# pullupcount.net
KiCad netlist of a schematic drawn in Altium Designer
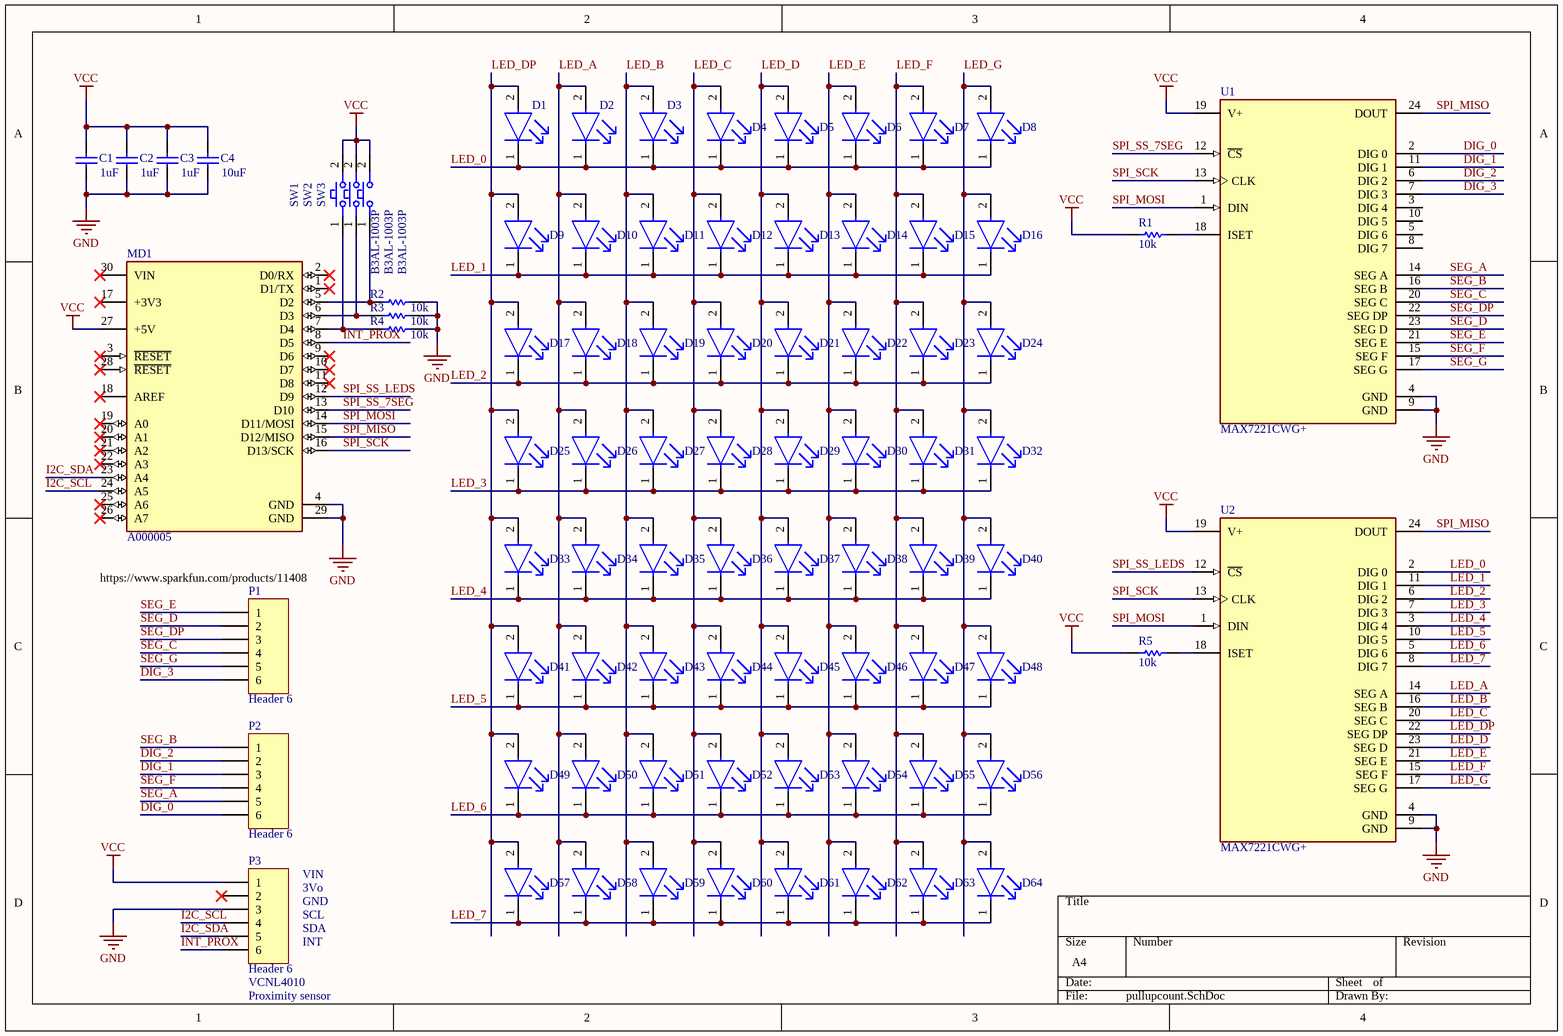
[diagram p0: pullupcount.SchDoc]

(export (version "E")
  (design (tool "Eeschema 10.0.6"))
  (components
    (comp (ref "C1")
      (value "1uF")
      (footprint "CAPC1608X90X35LL10T15")
      (fields (field (name "MANUFACTURER") "Murata") (field (name "PART NUMBER") "GRM188R61E105KA12D"))
      (libsource (lib "Altium Content Vault") (part "CAP"))
    )
    (comp (ref "C2")
      (value "1uF")
      (footprint "CAPC1608X90X35LL10T15")
      (fields (field (name "MANUFACTURER") "Murata") (field (name "PART NUMBER") "GRM188R61E105KA12D"))
      (libsource (lib "Altium Content Vault") (part "CAP"))
    )
    (comp (ref "C3")
      (value "1uF")
      (footprint "CAPC1608X90X35LL10T15")
      (fields (field (name "MANUFACTURER") "Murata") (field (name "PART NUMBER") "GRM188R61E105KA12D"))
      (libsource (lib "Altium Content Vault") (part "CAP"))
    )
    (comp (ref "C4")
      (value "10uF")
      (footprint "CAPC1608X90X35LL10T15")
      (fields (field (name "MANUFACTURER") "Murata") (field (name "PART NUMBER") "GRM188R61E105KA12D"))
      (libsource (lib "Altium Content Vault") (part "CAP"))
    )
    (comp (ref "D1")
      (value "LTST-C191TBKT")
      (footprint "FP-LTST-C191TBKT-MFG")
      (description "LED BLUE CLEAR CHIP SMD")
      (libsource (lib "Altium Content Vault") (part "8706943c75ba83719d021d2fdc84c58"))
    )
    (comp (ref "D2")
      (value "LTST-C191TBKT")
      (footprint "FP-LTST-C191TBKT-MFG")
      (description "LED BLUE CLEAR CHIP SMD")
      (libsource (lib "Altium Content Vault") (part "8706943c75ba83719d021d2fdc84c58"))
    )
    (comp (ref "D3")
      (value "LTST-C191TBKT")
      (footprint "FP-LTST-C191TBKT-MFG")
      (description "LED BLUE CLEAR CHIP SMD")
      (libsource (lib "Altium Content Vault") (part "8706943c75ba83719d021d2fdc84c58"))
    )
    (comp (ref "D4")
      (value "LTST-C191TBKT")
      (footprint "FP-LTST-C191TBKT-MFG")
      (description "LED BLUE CLEAR CHIP SMD")
      (libsource (lib "Altium Content Vault") (part "8706943c75ba83719d021d2fdc84c58"))
    )
    (comp (ref "D5")
      (value "LTST-C191TBKT")
      (footprint "FP-LTST-C191TBKT-MFG")
      (description "LED BLUE CLEAR CHIP SMD")
      (libsource (lib "Altium Content Vault") (part "8706943c75ba83719d021d2fdc84c58"))
    )
    (comp (ref "D6")
      (value "LTST-C191TBKT")
      (footprint "FP-LTST-C191TBKT-MFG")
      (description "LED BLUE CLEAR CHIP SMD")
      (libsource (lib "Altium Content Vault") (part "8706943c75ba83719d021d2fdc84c58"))
    )
    (comp (ref "D7")
      (value "LTST-C191TBKT")
      (footprint "FP-LTST-C191TBKT-MFG")
      (description "LED BLUE CLEAR CHIP SMD")
      (libsource (lib "Altium Content Vault") (part "8706943c75ba83719d021d2fdc84c58"))
    )
    (comp (ref "D8")
      (value "LTST-C191TBKT")
      (footprint "FP-LTST-C191TBKT-MFG")
      (description "LED BLUE CLEAR CHIP SMD")
      (libsource (lib "Altium Content Vault") (part "8706943c75ba83719d021d2fdc84c58"))
    )
    (comp (ref "D9")
      (value "LTST-C191TBKT")
      (footprint "FP-LTST-C191TBKT-MFG")
      (description "LED BLUE CLEAR CHIP SMD")
      (libsource (lib "Altium Content Vault") (part "8706943c75ba83719d021d2fdc84c58"))
    )
    (comp (ref "D10")
      (value "LTST-C191TBKT")
      (footprint "FP-LTST-C191TBKT-MFG")
      (description "LED BLUE CLEAR CHIP SMD")
      (libsource (lib "Altium Content Vault") (part "8706943c75ba83719d021d2fdc84c58"))
    )
    (comp (ref "D11")
      (value "LTST-C191TBKT")
      (footprint "FP-LTST-C191TBKT-MFG")
      (description "LED BLUE CLEAR CHIP SMD")
      (libsource (lib "Altium Content Vault") (part "8706943c75ba83719d021d2fdc84c58"))
    )
    (comp (ref "D12")
      (value "LTST-C191TBKT")
      (footprint "FP-LTST-C191TBKT-MFG")
      (description "LED BLUE CLEAR CHIP SMD")
      (libsource (lib "Altium Content Vault") (part "8706943c75ba83719d021d2fdc84c58"))
    )
    (comp (ref "D13")
      (value "LTST-C191TBKT")
      (footprint "FP-LTST-C191TBKT-MFG")
      (description "LED BLUE CLEAR CHIP SMD")
      (libsource (lib "Altium Content Vault") (part "8706943c75ba83719d021d2fdc84c58"))
    )
    (comp (ref "D14")
      (value "LTST-C191TBKT")
      (footprint "FP-LTST-C191TBKT-MFG")
      (description "LED BLUE CLEAR CHIP SMD")
      (libsource (lib "Altium Content Vault") (part "8706943c75ba83719d021d2fdc84c58"))
    )
    (comp (ref "D15")
      (value "LTST-C191TBKT")
      (footprint "FP-LTST-C191TBKT-MFG")
      (description "LED BLUE CLEAR CHIP SMD")
      (libsource (lib "Altium Content Vault") (part "8706943c75ba83719d021d2fdc84c58"))
    )
    (comp (ref "D16")
      (value "LTST-C191TBKT")
      (footprint "FP-LTST-C191TBKT-MFG")
      (description "LED BLUE CLEAR CHIP SMD")
      (libsource (lib "Altium Content Vault") (part "8706943c75ba83719d021d2fdc84c58"))
    )
    (comp (ref "D17")
      (value "LTST-C191TBKT")
      (footprint "FP-LTST-C191TBKT-MFG")
      (description "LED BLUE CLEAR CHIP SMD")
      (libsource (lib "Altium Content Vault") (part "8706943c75ba83719d021d2fdc84c58"))
    )
    (comp (ref "D18")
      (value "LTST-C191TBKT")
      (footprint "FP-LTST-C191TBKT-MFG")
      (description "LED BLUE CLEAR CHIP SMD")
      (libsource (lib "Altium Content Vault") (part "8706943c75ba83719d021d2fdc84c58"))
    )
    (comp (ref "D19")
      (value "LTST-C191TBKT")
      (footprint "FP-LTST-C191TBKT-MFG")
      (description "LED BLUE CLEAR CHIP SMD")
      (libsource (lib "Altium Content Vault") (part "8706943c75ba83719d021d2fdc84c58"))
    )
    (comp (ref "D20")
      (value "LTST-C191TBKT")
      (footprint "FP-LTST-C191TBKT-MFG")
      (description "LED BLUE CLEAR CHIP SMD")
      (libsource (lib "Altium Content Vault") (part "8706943c75ba83719d021d2fdc84c58"))
    )
    (comp (ref "D21")
      (value "LTST-C191TBKT")
      (footprint "FP-LTST-C191TBKT-MFG")
      (description "LED BLUE CLEAR CHIP SMD")
      (libsource (lib "Altium Content Vault") (part "8706943c75ba83719d021d2fdc84c58"))
    )
    (comp (ref "D22")
      (value "LTST-C191TBKT")
      (footprint "FP-LTST-C191TBKT-MFG")
      (description "LED BLUE CLEAR CHIP SMD")
      (libsource (lib "Altium Content Vault") (part "8706943c75ba83719d021d2fdc84c58"))
    )
    (comp (ref "D23")
      (value "LTST-C191TBKT")
      (footprint "FP-LTST-C191TBKT-MFG")
      (description "LED BLUE CLEAR CHIP SMD")
      (libsource (lib "Altium Content Vault") (part "8706943c75ba83719d021d2fdc84c58"))
    )
    (comp (ref "D24")
      (value "LTST-C191TBKT")
      (footprint "FP-LTST-C191TBKT-MFG")
      (description "LED BLUE CLEAR CHIP SMD")
      (libsource (lib "Altium Content Vault") (part "8706943c75ba83719d021d2fdc84c58"))
    )
    (comp (ref "D25")
      (value "LTST-C191TBKT")
      (footprint "FP-LTST-C191TBKT-MFG")
      (description "LED BLUE CLEAR CHIP SMD")
      (libsource (lib "Altium Content Vault") (part "8706943c75ba83719d021d2fdc84c58"))
    )
    (comp (ref "D26")
      (value "LTST-C191TBKT")
      (footprint "FP-LTST-C191TBKT-MFG")
      (description "LED BLUE CLEAR CHIP SMD")
      (libsource (lib "Altium Content Vault") (part "8706943c75ba83719d021d2fdc84c58"))
    )
    (comp (ref "D27")
      (value "LTST-C191TBKT")
      (footprint "FP-LTST-C191TBKT-MFG")
      (description "LED BLUE CLEAR CHIP SMD")
      (libsource (lib "Altium Content Vault") (part "8706943c75ba83719d021d2fdc84c58"))
    )
    (comp (ref "D28")
      (value "LTST-C191TBKT")
      (footprint "FP-LTST-C191TBKT-MFG")
      (description "LED BLUE CLEAR CHIP SMD")
      (libsource (lib "Altium Content Vault") (part "8706943c75ba83719d021d2fdc84c58"))
    )
    (comp (ref "D29")
      (value "LTST-C191TBKT")
      (footprint "FP-LTST-C191TBKT-MFG")
      (description "LED BLUE CLEAR CHIP SMD")
      (libsource (lib "Altium Content Vault") (part "8706943c75ba83719d021d2fdc84c58"))
    )
    (comp (ref "D30")
      (value "LTST-C191TBKT")
      (footprint "FP-LTST-C191TBKT-MFG")
      (description "LED BLUE CLEAR CHIP SMD")
      (libsource (lib "Altium Content Vault") (part "8706943c75ba83719d021d2fdc84c58"))
    )
    (comp (ref "D31")
      (value "LTST-C191TBKT")
      (footprint "FP-LTST-C191TBKT-MFG")
      (description "LED BLUE CLEAR CHIP SMD")
      (libsource (lib "Altium Content Vault") (part "8706943c75ba83719d021d2fdc84c58"))
    )
    (comp (ref "D32")
      (value "LTST-C191TBKT")
      (footprint "FP-LTST-C191TBKT-MFG")
      (description "LED BLUE CLEAR CHIP SMD")
      (libsource (lib "Altium Content Vault") (part "8706943c75ba83719d021d2fdc84c58"))
    )
    (comp (ref "D33")
      (value "LTST-C191TBKT")
      (footprint "FP-LTST-C191TBKT-MFG")
      (description "LED BLUE CLEAR CHIP SMD")
      (libsource (lib "Altium Content Vault") (part "8706943c75ba83719d021d2fdc84c58"))
    )
    (comp (ref "D34")
      (value "LTST-C191TBKT")
      (footprint "FP-LTST-C191TBKT-MFG")
      (description "LED BLUE CLEAR CHIP SMD")
      (libsource (lib "Altium Content Vault") (part "8706943c75ba83719d021d2fdc84c58"))
    )
    (comp (ref "D35")
      (value "LTST-C191TBKT")
      (footprint "FP-LTST-C191TBKT-MFG")
      (description "LED BLUE CLEAR CHIP SMD")
      (libsource (lib "Altium Content Vault") (part "8706943c75ba83719d021d2fdc84c58"))
    )
    (comp (ref "D36")
      (value "LTST-C191TBKT")
      (footprint "FP-LTST-C191TBKT-MFG")
      (description "LED BLUE CLEAR CHIP SMD")
      (libsource (lib "Altium Content Vault") (part "8706943c75ba83719d021d2fdc84c58"))
    )
    (comp (ref "D37")
      (value "LTST-C191TBKT")
      (footprint "FP-LTST-C191TBKT-MFG")
      (description "LED BLUE CLEAR CHIP SMD")
      (libsource (lib "Altium Content Vault") (part "8706943c75ba83719d021d2fdc84c58"))
    )
    (comp (ref "D38")
      (value "LTST-C191TBKT")
      (footprint "FP-LTST-C191TBKT-MFG")
      (description "LED BLUE CLEAR CHIP SMD")
      (libsource (lib "Altium Content Vault") (part "8706943c75ba83719d021d2fdc84c58"))
    )
    (comp (ref "D39")
      (value "LTST-C191TBKT")
      (footprint "FP-LTST-C191TBKT-MFG")
      (description "LED BLUE CLEAR CHIP SMD")
      (libsource (lib "Altium Content Vault") (part "8706943c75ba83719d021d2fdc84c58"))
    )
    (comp (ref "D40")
      (value "LTST-C191TBKT")
      (footprint "FP-LTST-C191TBKT-MFG")
      (description "LED BLUE CLEAR CHIP SMD")
      (libsource (lib "Altium Content Vault") (part "8706943c75ba83719d021d2fdc84c58"))
    )
    (comp (ref "D41")
      (value "LTST-C191TBKT")
      (footprint "FP-LTST-C191TBKT-MFG")
      (description "LED BLUE CLEAR CHIP SMD")
      (libsource (lib "Altium Content Vault") (part "8706943c75ba83719d021d2fdc84c58"))
    )
    (comp (ref "D42")
      (value "LTST-C191TBKT")
      (footprint "FP-LTST-C191TBKT-MFG")
      (description "LED BLUE CLEAR CHIP SMD")
      (libsource (lib "Altium Content Vault") (part "8706943c75ba83719d021d2fdc84c58"))
    )
    (comp (ref "D43")
      (value "LTST-C191TBKT")
      (footprint "FP-LTST-C191TBKT-MFG")
      (description "LED BLUE CLEAR CHIP SMD")
      (libsource (lib "Altium Content Vault") (part "8706943c75ba83719d021d2fdc84c58"))
    )
    (comp (ref "D44")
      (value "LTST-C191TBKT")
      (footprint "FP-LTST-C191TBKT-MFG")
      (description "LED BLUE CLEAR CHIP SMD")
      (libsource (lib "Altium Content Vault") (part "8706943c75ba83719d021d2fdc84c58"))
    )
    (comp (ref "D45")
      (value "LTST-C191TBKT")
      (footprint "FP-LTST-C191TBKT-MFG")
      (description "LED BLUE CLEAR CHIP SMD")
      (libsource (lib "Altium Content Vault") (part "8706943c75ba83719d021d2fdc84c58"))
    )
    (comp (ref "D46")
      (value "LTST-C191TBKT")
      (footprint "FP-LTST-C191TBKT-MFG")
      (description "LED BLUE CLEAR CHIP SMD")
      (libsource (lib "Altium Content Vault") (part "8706943c75ba83719d021d2fdc84c58"))
    )
    (comp (ref "D47")
      (value "LTST-C191TBKT")
      (footprint "FP-LTST-C191TBKT-MFG")
      (description "LED BLUE CLEAR CHIP SMD")
      (libsource (lib "Altium Content Vault") (part "8706943c75ba83719d021d2fdc84c58"))
    )
    (comp (ref "D48")
      (value "LTST-C191TBKT")
      (footprint "FP-LTST-C191TBKT-MFG")
      (description "LED BLUE CLEAR CHIP SMD")
      (libsource (lib "Altium Content Vault") (part "8706943c75ba83719d021d2fdc84c58"))
    )
    (comp (ref "D49")
      (value "LTST-C191TBKT")
      (footprint "FP-LTST-C191TBKT-MFG")
      (description "LED BLUE CLEAR CHIP SMD")
      (libsource (lib "Altium Content Vault") (part "8706943c75ba83719d021d2fdc84c58"))
    )
    (comp (ref "D50")
      (value "LTST-C191TBKT")
      (footprint "FP-LTST-C191TBKT-MFG")
      (description "LED BLUE CLEAR CHIP SMD")
      (libsource (lib "Altium Content Vault") (part "8706943c75ba83719d021d2fdc84c58"))
    )
    (comp (ref "D51")
      (value "LTST-C191TBKT")
      (footprint "FP-LTST-C191TBKT-MFG")
      (description "LED BLUE CLEAR CHIP SMD")
      (libsource (lib "Altium Content Vault") (part "8706943c75ba83719d021d2fdc84c58"))
    )
    (comp (ref "D52")
      (value "LTST-C191TBKT")
      (footprint "FP-LTST-C191TBKT-MFG")
      (description "LED BLUE CLEAR CHIP SMD")
      (libsource (lib "Altium Content Vault") (part "8706943c75ba83719d021d2fdc84c58"))
    )
    (comp (ref "D53")
      (value "LTST-C191TBKT")
      (footprint "FP-LTST-C191TBKT-MFG")
      (description "LED BLUE CLEAR CHIP SMD")
      (libsource (lib "Altium Content Vault") (part "8706943c75ba83719d021d2fdc84c58"))
    )
    (comp (ref "D54")
      (value "LTST-C191TBKT")
      (footprint "FP-LTST-C191TBKT-MFG")
      (description "LED BLUE CLEAR CHIP SMD")
      (libsource (lib "Altium Content Vault") (part "8706943c75ba83719d021d2fdc84c58"))
    )
    (comp (ref "D55")
      (value "LTST-C191TBKT")
      (footprint "FP-LTST-C191TBKT-MFG")
      (description "LED BLUE CLEAR CHIP SMD")
      (libsource (lib "Altium Content Vault") (part "8706943c75ba83719d021d2fdc84c58"))
    )
    (comp (ref "D56")
      (value "LTST-C191TBKT")
      (footprint "FP-LTST-C191TBKT-MFG")
      (description "LED BLUE CLEAR CHIP SMD")
      (libsource (lib "Altium Content Vault") (part "8706943c75ba83719d021d2fdc84c58"))
    )
    (comp (ref "D57")
      (value "LTST-C191TBKT")
      (footprint "FP-LTST-C191TBKT-MFG")
      (description "LED BLUE CLEAR CHIP SMD")
      (libsource (lib "Altium Content Vault") (part "8706943c75ba83719d021d2fdc84c58"))
    )
    (comp (ref "D58")
      (value "LTST-C191TBKT")
      (footprint "FP-LTST-C191TBKT-MFG")
      (description "LED BLUE CLEAR CHIP SMD")
      (libsource (lib "Altium Content Vault") (part "8706943c75ba83719d021d2fdc84c58"))
    )
    (comp (ref "D59")
      (value "LTST-C191TBKT")
      (footprint "FP-LTST-C191TBKT-MFG")
      (description "LED BLUE CLEAR CHIP SMD")
      (libsource (lib "Altium Content Vault") (part "8706943c75ba83719d021d2fdc84c58"))
    )
    (comp (ref "D60")
      (value "LTST-C191TBKT")
      (footprint "FP-LTST-C191TBKT-MFG")
      (description "LED BLUE CLEAR CHIP SMD")
      (libsource (lib "Altium Content Vault") (part "8706943c75ba83719d021d2fdc84c58"))
    )
    (comp (ref "D61")
      (value "LTST-C191TBKT")
      (footprint "FP-LTST-C191TBKT-MFG")
      (description "LED BLUE CLEAR CHIP SMD")
      (libsource (lib "Altium Content Vault") (part "8706943c75ba83719d021d2fdc84c58"))
    )
    (comp (ref "D62")
      (value "LTST-C191TBKT")
      (footprint "FP-LTST-C191TBKT-MFG")
      (description "LED BLUE CLEAR CHIP SMD")
      (libsource (lib "Altium Content Vault") (part "8706943c75ba83719d021d2fdc84c58"))
    )
    (comp (ref "D63")
      (value "LTST-C191TBKT")
      (footprint "FP-LTST-C191TBKT-MFG")
      (description "LED BLUE CLEAR CHIP SMD")
      (libsource (lib "Altium Content Vault") (part "8706943c75ba83719d021d2fdc84c58"))
    )
    (comp (ref "D64")
      (value "LTST-C191TBKT")
      (footprint "FP-LTST-C191TBKT-MFG")
      (description "LED BLUE CLEAR CHIP SMD")
      (libsource (lib "Altium Content Vault") (part "8706943c75ba83719d021d2fdc84c58"))
    )
    (comp (ref "MD1")
      (value "A000005")
      (footprint "FP-A000005-MFG")
      (description "ARDUINO NANO ATMEGA328 EVAL BRD")
      (libsource (lib "Altium Content Vault") (part "d190c066e99afd1c6882cf92e11b2cc"))
    )
    (comp (ref "P1")
      (value "Header 6")
      (footprint "HDR1X6")
      (description "Header, 6-Pin")
      (fields (field (name "PUBLISHER") "Altium Limited"))
      (libsource (lib "Miscellaneous Connectors") (part "Header 6"))
    )
    (comp (ref "P2")
      (value "Header 6")
      (footprint "HDR1X6")
      (description "Header, 6-Pin")
      (fields (field (name "PUBLISHER") "Altium Limited"))
      (libsource (lib "Miscellaneous Connectors") (part "Header 6"))
    )
    (comp (ref "P3")
      (value "Header 6")
      (footprint "HDR1X6")
      (description "Header, 6-Pin")
      (fields (field (name "PUBLISHER") "Altium Limited"))
      (libsource (lib "Miscellaneous Connectors") (part "Header 6"))
    )
    (comp (ref "R1")
      (value "10k")
      (footprint "RESC1609X50X30NL8T20")
      (description "Chip Resistor, 10 KOhm, +/- 1%, 100 mW, -55 to 155 degC, 0603 (1608 Metric), RoHS, Tape and Reel")
      (fields (field (name "MANUFACTURER") "Vishay Semiconductor"))
      (libsource (lib "Altium Content Vault") (part "RES-2"))
    )
    (comp (ref "R2")
      (value "10k")
      (footprint "RESC1609X50X30NL8T20")
      (description "Chip Resistor, 10 KOhm, +/- 1%, 100 mW, -55 to 155 degC, 0603 (1608 Metric), RoHS, Tape and Reel")
      (fields (field (name "MANUFACTURER") "Vishay Semiconductor"))
      (libsource (lib "Altium Content Vault") (part "RES-2"))
    )
    (comp (ref "R3")
      (value "10k")
      (footprint "RESC1609X50X30NL8T20")
      (description "Chip Resistor, 10 KOhm, +/- 1%, 100 mW, -55 to 155 degC, 0603 (1608 Metric), RoHS, Tape and Reel")
      (fields (field (name "MANUFACTURER") "Vishay Semiconductor"))
      (libsource (lib "Altium Content Vault") (part "RES-2"))
    )
    (comp (ref "R4")
      (value "10k")
      (footprint "RESC1609X50X30NL8T20")
      (description "Chip Resistor, 10 KOhm, +/- 1%, 100 mW, -55 to 155 degC, 0603 (1608 Metric), RoHS, Tape and Reel")
      (fields (field (name "MANUFACTURER") "Vishay Semiconductor"))
      (libsource (lib "Altium Content Vault") (part "RES-2"))
    )
    (comp (ref "R5")
      (value "10k")
      (footprint "RESC1609X50X30NL8T20")
      (description "Chip Resistor, 10 KOhm, +/- 1%, 100 mW, -55 to 155 degC, 0603 (1608 Metric), RoHS, Tape and Reel")
      (fields (field (name "MANUFACTURER") "Vishay Semiconductor"))
      (libsource (lib "Altium Content Vault") (part "RES-2"))
    )
    (comp (ref "SW1")
      (value "B3AL-1003P")
      (footprint "FP-B3AL-1003P-MFG")
      (description "SWITCH TACTILE SPST-NO 0.05A 16V")
      (libsource (lib "Altium Content Vault") (part "69e8347f6a24c021ef43a914a4df441"))
    )
    (comp (ref "SW2")
      (value "B3AL-1003P")
      (footprint "FP-B3AL-1003P-MFG")
      (description "SWITCH TACTILE SPST-NO 0.05A 16V")
      (libsource (lib "Altium Content Vault") (part "69e8347f6a24c021ef43a914a4df441"))
    )
    (comp (ref "SW3")
      (value "B3AL-1003P")
      (footprint "FP-B3AL-1003P-MFG")
      (description "SWITCH TACTILE SPST-NO 0.05A 16V")
      (libsource (lib "Altium Content Vault") (part "69e8347f6a24c021ef43a914a4df441"))
    )
    (comp (ref "U1")
      (value "MAX7221CWG+")
      (footprint "FP-W24-1-MFG")
      (description "IC DRVR 7 SEGMNT 8 DIGIT 24SOIC")
      (fields
        (field (name "MANUFACTURER") "Maxim Integrated")
        (field (name "OCTOPART") "https://octopart.com/max7221cwg%2B-maxim+integrated-39581478")
      )
      (libsource (lib "Altium Content Vault") (part "a71a82daf51cffeecc638e415d68d56"))
    )
    (comp (ref "U2")
      (value "MAX7221CWG+")
      (footprint "FP-W24-1-MFG")
      (description "IC DRVR 7 SEGMNT 8 DIGIT 24SOIC")
      (fields
        (field (name "MANUFACTURER") "Maxim Integrated")
        (field (name "OCTOPART") "https://octopart.com/max7221cwg%2B-maxim+integrated-39581478")
      )
      (libsource (lib "Altium Content Vault") (part "a71a82daf51cffeecc638e415d68d56"))
    )
  )
  (nets
    (net (code "1") (name "/DIG_0") (class "Default")
      (node (ref "P2") (pin "6") (pinfunction "6_6") (pintype "passive"))
      (node (ref "U1") (pin "2") (pinfunction "DIG_0_2") (pintype "passive"))
    )
    (net (code "2") (name "/DIG_1") (class "Default")
      (node (ref "P2") (pin "3") (pinfunction "3_3") (pintype "passive"))
      (node (ref "U1") (pin "11") (pinfunction "DIG_1_11") (pintype "passive"))
    )
    (net (code "3") (name "/DIG_2") (class "Default")
      (node (ref "P2") (pin "2") (pinfunction "2_2") (pintype "passive"))
      (node (ref "U1") (pin "6") (pinfunction "DIG_2_6") (pintype "passive"))
    )
    (net (code "4") (name "/DIG_3") (class "Default")
      (node (ref "P1") (pin "6") (pinfunction "6_6") (pintype "passive"))
      (node (ref "U1") (pin "7") (pinfunction "DIG_3_7") (pintype "passive"))
    )
    (net (code "5") (name "/I2C_SCL") (class "Default")
      (node (ref "MD1") (pin "24") (pinfunction "A5_24") (pintype "bidirectional"))
      (node (ref "P3") (pin "4") (pinfunction "4_4") (pintype "passive"))
    )
    (net (code "6") (name "/I2C_SDA") (class "Default")
      (node (ref "MD1") (pin "23") (pinfunction "A4_23") (pintype "bidirectional"))
      (node (ref "P3") (pin "5") (pinfunction "5_5") (pintype "passive"))
    )
    (net (code "7") (name "/INT_PROX") (class "Default")
      (node (ref "MD1") (pin "8") (pinfunction "D5_8") (pintype "bidirectional"))
      (node (ref "P3") (pin "6") (pinfunction "6_6") (pintype "passive"))
    )
    (net (code "8") (name "/LED_0") (class "Default")
      (node (ref "D1") (pin "1") (pinfunction "C_1") (pintype "passive"))
      (node (ref "D2") (pin "1") (pinfunction "C_1") (pintype "passive"))
      (node (ref "D3") (pin "1") (pinfunction "C_1") (pintype "passive"))
      (node (ref "D4") (pin "1") (pinfunction "C_1") (pintype "passive"))
      (node (ref "D5") (pin "1") (pinfunction "C_1") (pintype "passive"))
      (node (ref "D6") (pin "1") (pinfunction "C_1") (pintype "passive"))
      (node (ref "D7") (pin "1") (pinfunction "C_1") (pintype "passive"))
      (node (ref "D8") (pin "1") (pinfunction "C_1") (pintype "passive"))
      (node (ref "U2") (pin "2") (pinfunction "DIG_0_2") (pintype "passive"))
    )
    (net (code "9") (name "/LED_1") (class "Default")
      (node (ref "D10") (pin "1") (pinfunction "C_1") (pintype "passive"))
      (node (ref "D11") (pin "1") (pinfunction "C_1") (pintype "passive"))
      (node (ref "D12") (pin "1") (pinfunction "C_1") (pintype "passive"))
      (node (ref "D13") (pin "1") (pinfunction "C_1") (pintype "passive"))
      (node (ref "D14") (pin "1") (pinfunction "C_1") (pintype "passive"))
      (node (ref "D15") (pin "1") (pinfunction "C_1") (pintype "passive"))
      (node (ref "D16") (pin "1") (pinfunction "C_1") (pintype "passive"))
      (node (ref "D9") (pin "1") (pinfunction "C_1") (pintype "passive"))
      (node (ref "U2") (pin "11") (pinfunction "DIG_1_11") (pintype "passive"))
    )
    (net (code "10") (name "/LED_2") (class "Default")
      (node (ref "D17") (pin "1") (pinfunction "C_1") (pintype "passive"))
      (node (ref "D18") (pin "1") (pinfunction "C_1") (pintype "passive"))
      (node (ref "D19") (pin "1") (pinfunction "C_1") (pintype "passive"))
      (node (ref "D20") (pin "1") (pinfunction "C_1") (pintype "passive"))
      (node (ref "D21") (pin "1") (pinfunction "C_1") (pintype "passive"))
      (node (ref "D22") (pin "1") (pinfunction "C_1") (pintype "passive"))
      (node (ref "D23") (pin "1") (pinfunction "C_1") (pintype "passive"))
      (node (ref "D24") (pin "1") (pinfunction "C_1") (pintype "passive"))
      (node (ref "U2") (pin "6") (pinfunction "DIG_2_6") (pintype "passive"))
    )
    (net (code "11") (name "/LED_3") (class "Default")
      (node (ref "D25") (pin "1") (pinfunction "C_1") (pintype "passive"))
      (node (ref "D26") (pin "1") (pinfunction "C_1") (pintype "passive"))
      (node (ref "D27") (pin "1") (pinfunction "C_1") (pintype "passive"))
      (node (ref "D28") (pin "1") (pinfunction "C_1") (pintype "passive"))
      (node (ref "D29") (pin "1") (pinfunction "C_1") (pintype "passive"))
      (node (ref "D30") (pin "1") (pinfunction "C_1") (pintype "passive"))
      (node (ref "D31") (pin "1") (pinfunction "C_1") (pintype "passive"))
      (node (ref "D32") (pin "1") (pinfunction "C_1") (pintype "passive"))
      (node (ref "U2") (pin "7") (pinfunction "DIG_3_7") (pintype "passive"))
    )
    (net (code "12") (name "/LED_4") (class "Default")
      (node (ref "D33") (pin "1") (pinfunction "C_1") (pintype "passive"))
      (node (ref "D34") (pin "1") (pinfunction "C_1") (pintype "passive"))
      (node (ref "D35") (pin "1") (pinfunction "C_1") (pintype "passive"))
      (node (ref "D36") (pin "1") (pinfunction "C_1") (pintype "passive"))
      (node (ref "D37") (pin "1") (pinfunction "C_1") (pintype "passive"))
      (node (ref "D38") (pin "1") (pinfunction "C_1") (pintype "passive"))
      (node (ref "D39") (pin "1") (pinfunction "C_1") (pintype "passive"))
      (node (ref "D40") (pin "1") (pinfunction "C_1") (pintype "passive"))
      (node (ref "U2") (pin "3") (pinfunction "DIG_4_3") (pintype "passive"))
    )
    (net (code "13") (name "/LED_5") (class "Default")
      (node (ref "D41") (pin "1") (pinfunction "C_1") (pintype "passive"))
      (node (ref "D42") (pin "1") (pinfunction "C_1") (pintype "passive"))
      (node (ref "D43") (pin "1") (pinfunction "C_1") (pintype "passive"))
      (node (ref "D44") (pin "1") (pinfunction "C_1") (pintype "passive"))
      (node (ref "D45") (pin "1") (pinfunction "C_1") (pintype "passive"))
      (node (ref "D46") (pin "1") (pinfunction "C_1") (pintype "passive"))
      (node (ref "D47") (pin "1") (pinfunction "C_1") (pintype "passive"))
      (node (ref "D48") (pin "1") (pinfunction "C_1") (pintype "passive"))
      (node (ref "U2") (pin "10") (pinfunction "DIG_5_10") (pintype "passive"))
    )
    (net (code "14") (name "/LED_6") (class "Default")
      (node (ref "D49") (pin "1") (pinfunction "C_1") (pintype "passive"))
      (node (ref "D50") (pin "1") (pinfunction "C_1") (pintype "passive"))
      (node (ref "D51") (pin "1") (pinfunction "C_1") (pintype "passive"))
      (node (ref "D52") (pin "1") (pinfunction "C_1") (pintype "passive"))
      (node (ref "D53") (pin "1") (pinfunction "C_1") (pintype "passive"))
      (node (ref "D54") (pin "1") (pinfunction "C_1") (pintype "passive"))
      (node (ref "D55") (pin "1") (pinfunction "C_1") (pintype "passive"))
      (node (ref "D56") (pin "1") (pinfunction "C_1") (pintype "passive"))
      (node (ref "U2") (pin "5") (pinfunction "DIG_6_5") (pintype "passive"))
    )
    (net (code "15") (name "/LED_7") (class "Default")
      (node (ref "D57") (pin "1") (pinfunction "C_1") (pintype "passive"))
      (node (ref "D58") (pin "1") (pinfunction "C_1") (pintype "passive"))
      (node (ref "D59") (pin "1") (pinfunction "C_1") (pintype "passive"))
      (node (ref "D60") (pin "1") (pinfunction "C_1") (pintype "passive"))
      (node (ref "D61") (pin "1") (pinfunction "C_1") (pintype "passive"))
      (node (ref "D62") (pin "1") (pinfunction "C_1") (pintype "passive"))
      (node (ref "D63") (pin "1") (pinfunction "C_1") (pintype "passive"))
      (node (ref "D64") (pin "1") (pinfunction "C_1") (pintype "passive"))
      (node (ref "U2") (pin "8") (pinfunction "DIG_7_8") (pintype "passive"))
    )
    (net (code "16") (name "/LED_A") (class "Default")
      (node (ref "D10") (pin "2") (pinfunction "A_2") (pintype "passive"))
      (node (ref "D18") (pin "2") (pinfunction "A_2") (pintype "passive"))
      (node (ref "D2") (pin "2") (pinfunction "A_2") (pintype "passive"))
      (node (ref "D26") (pin "2") (pinfunction "A_2") (pintype "passive"))
      (node (ref "D34") (pin "2") (pinfunction "A_2") (pintype "passive"))
      (node (ref "D42") (pin "2") (pinfunction "A_2") (pintype "passive"))
      (node (ref "D50") (pin "2") (pinfunction "A_2") (pintype "passive"))
      (node (ref "D58") (pin "2") (pinfunction "A_2") (pintype "passive"))
      (node (ref "U2") (pin "14") (pinfunction "SEG_A_14") (pintype "passive"))
    )
    (net (code "17") (name "/LED_B") (class "Default")
      (node (ref "D11") (pin "2") (pinfunction "A_2") (pintype "passive"))
      (node (ref "D19") (pin "2") (pinfunction "A_2") (pintype "passive"))
      (node (ref "D27") (pin "2") (pinfunction "A_2") (pintype "passive"))
      (node (ref "D3") (pin "2") (pinfunction "A_2") (pintype "passive"))
      (node (ref "D35") (pin "2") (pinfunction "A_2") (pintype "passive"))
      (node (ref "D43") (pin "2") (pinfunction "A_2") (pintype "passive"))
      (node (ref "D51") (pin "2") (pinfunction "A_2") (pintype "passive"))
      (node (ref "D59") (pin "2") (pinfunction "A_2") (pintype "passive"))
      (node (ref "U2") (pin "16") (pinfunction "SEG_B_16") (pintype "passive"))
    )
    (net (code "18") (name "/LED_C") (class "Default")
      (node (ref "D12") (pin "2") (pinfunction "A_2") (pintype "passive"))
      (node (ref "D20") (pin "2") (pinfunction "A_2") (pintype "passive"))
      (node (ref "D28") (pin "2") (pinfunction "A_2") (pintype "passive"))
      (node (ref "D36") (pin "2") (pinfunction "A_2") (pintype "passive"))
      (node (ref "D4") (pin "2") (pinfunction "A_2") (pintype "passive"))
      (node (ref "D44") (pin "2") (pinfunction "A_2") (pintype "passive"))
      (node (ref "D52") (pin "2") (pinfunction "A_2") (pintype "passive"))
      (node (ref "D60") (pin "2") (pinfunction "A_2") (pintype "passive"))
      (node (ref "U2") (pin "20") (pinfunction "SEG_C_20") (pintype "passive"))
    )
    (net (code "19") (name "/LED_D") (class "Default")
      (node (ref "D13") (pin "2") (pinfunction "A_2") (pintype "passive"))
      (node (ref "D21") (pin "2") (pinfunction "A_2") (pintype "passive"))
      (node (ref "D29") (pin "2") (pinfunction "A_2") (pintype "passive"))
      (node (ref "D37") (pin "2") (pinfunction "A_2") (pintype "passive"))
      (node (ref "D45") (pin "2") (pinfunction "A_2") (pintype "passive"))
      (node (ref "D5") (pin "2") (pinfunction "A_2") (pintype "passive"))
      (node (ref "D53") (pin "2") (pinfunction "A_2") (pintype "passive"))
      (node (ref "D61") (pin "2") (pinfunction "A_2") (pintype "passive"))
      (node (ref "U2") (pin "23") (pinfunction "SEG_D_23") (pintype "passive"))
    )
    (net (code "20") (name "/LED_DP") (class "Default")
      (node (ref "D1") (pin "2") (pinfunction "A_2") (pintype "passive"))
      (node (ref "D17") (pin "2") (pinfunction "A_2") (pintype "passive"))
      (node (ref "D25") (pin "2") (pinfunction "A_2") (pintype "passive"))
      (node (ref "D33") (pin "2") (pinfunction "A_2") (pintype "passive"))
      (node (ref "D41") (pin "2") (pinfunction "A_2") (pintype "passive"))
      (node (ref "D49") (pin "2") (pinfunction "A_2") (pintype "passive"))
      (node (ref "D57") (pin "2") (pinfunction "A_2") (pintype "passive"))
      (node (ref "D9") (pin "2") (pinfunction "A_2") (pintype "passive"))
      (node (ref "U2") (pin "22") (pinfunction "SEG_DP_22") (pintype "passive"))
    )
    (net (code "21") (name "/LED_E") (class "Default")
      (node (ref "D14") (pin "2") (pinfunction "A_2") (pintype "passive"))
      (node (ref "D22") (pin "2") (pinfunction "A_2") (pintype "passive"))
      (node (ref "D30") (pin "2") (pinfunction "A_2") (pintype "passive"))
      (node (ref "D38") (pin "2") (pinfunction "A_2") (pintype "passive"))
      (node (ref "D46") (pin "2") (pinfunction "A_2") (pintype "passive"))
      (node (ref "D54") (pin "2") (pinfunction "A_2") (pintype "passive"))
      (node (ref "D6") (pin "2") (pinfunction "A_2") (pintype "passive"))
      (node (ref "D62") (pin "2") (pinfunction "A_2") (pintype "passive"))
      (node (ref "U2") (pin "21") (pinfunction "SEG_E_21") (pintype "passive"))
    )
    (net (code "22") (name "/LED_F") (class "Default")
      (node (ref "D15") (pin "2") (pinfunction "A_2") (pintype "passive"))
      (node (ref "D23") (pin "2") (pinfunction "A_2") (pintype "passive"))
      (node (ref "D31") (pin "2") (pinfunction "A_2") (pintype "passive"))
      (node (ref "D39") (pin "2") (pinfunction "A_2") (pintype "passive"))
      (node (ref "D47") (pin "2") (pinfunction "A_2") (pintype "passive"))
      (node (ref "D55") (pin "2") (pinfunction "A_2") (pintype "passive"))
      (node (ref "D63") (pin "2") (pinfunction "A_2") (pintype "passive"))
      (node (ref "D7") (pin "2") (pinfunction "A_2") (pintype "passive"))
      (node (ref "U2") (pin "15") (pinfunction "SEG_F_15") (pintype "passive"))
    )
    (net (code "23") (name "/LED_G") (class "Default")
      (node (ref "D16") (pin "2") (pinfunction "A_2") (pintype "passive"))
      (node (ref "D24") (pin "2") (pinfunction "A_2") (pintype "passive"))
      (node (ref "D32") (pin "2") (pinfunction "A_2") (pintype "passive"))
      (node (ref "D40") (pin "2") (pinfunction "A_2") (pintype "passive"))
      (node (ref "D48") (pin "2") (pinfunction "A_2") (pintype "passive"))
      (node (ref "D56") (pin "2") (pinfunction "A_2") (pintype "passive"))
      (node (ref "D64") (pin "2") (pinfunction "A_2") (pintype "passive"))
      (node (ref "D8") (pin "2") (pinfunction "A_2") (pintype "passive"))
      (node (ref "U2") (pin "17") (pinfunction "SEG_G_17") (pintype "passive"))
    )
    (net (code "24") (name "/SEG_A") (class "Default")
      (node (ref "P2") (pin "5") (pinfunction "5_5") (pintype "passive"))
      (node (ref "U1") (pin "14") (pinfunction "SEG_A_14") (pintype "passive"))
    )
    (net (code "25") (name "/SEG_B") (class "Default")
      (node (ref "P2") (pin "1") (pinfunction "1_1") (pintype "passive"))
      (node (ref "U1") (pin "16") (pinfunction "SEG_B_16") (pintype "passive"))
    )
    (net (code "26") (name "/SEG_C") (class "Default")
      (node (ref "P1") (pin "4") (pinfunction "4_4") (pintype "passive"))
      (node (ref "U1") (pin "20") (pinfunction "SEG_C_20") (pintype "passive"))
    )
    (net (code "27") (name "/SEG_D") (class "Default")
      (node (ref "P1") (pin "2") (pinfunction "2_2") (pintype "passive"))
      (node (ref "U1") (pin "23") (pinfunction "SEG_D_23") (pintype "passive"))
    )
    (net (code "28") (name "/SEG_DP") (class "Default")
      (node (ref "P1") (pin "3") (pinfunction "3_3") (pintype "passive"))
      (node (ref "U1") (pin "22") (pinfunction "SEG_DP_22") (pintype "passive"))
    )
    (net (code "29") (name "/SEG_E") (class "Default")
      (node (ref "P1") (pin "1") (pinfunction "1_1") (pintype "passive"))
      (node (ref "U1") (pin "21") (pinfunction "SEG_E_21") (pintype "passive"))
    )
    (net (code "30") (name "/SEG_F") (class "Default")
      (node (ref "P2") (pin "4") (pinfunction "4_4") (pintype "passive"))
      (node (ref "U1") (pin "15") (pinfunction "SEG_F_15") (pintype "passive"))
    )
    (net (code "31") (name "/SEG_G") (class "Default")
      (node (ref "P1") (pin "5") (pinfunction "5_5") (pintype "passive"))
      (node (ref "U1") (pin "17") (pinfunction "SEG_G_17") (pintype "passive"))
    )
    (net (code "32") (name "/SPI_MISO") (class "Default")
      (node (ref "MD1") (pin "15") (pinfunction "D12/MISO_15") (pintype "bidirectional"))
      (node (ref "U1") (pin "24") (pinfunction "DOUT_24") (pintype "passive"))
      (node (ref "U2") (pin "24") (pinfunction "DOUT_24") (pintype "passive"))
    )
    (net (code "33") (name "/SPI_MOSI") (class "Default")
      (node (ref "MD1") (pin "14") (pinfunction "D11/MOSI_14") (pintype "bidirectional"))
      (node (ref "U1") (pin "1") (pinfunction "DIN_1") (pintype "input"))
      (node (ref "U2") (pin "1") (pinfunction "DIN_1") (pintype "input"))
    )
    (net (code "34") (name "/SPI_SCK") (class "Default")
      (node (ref "MD1") (pin "16") (pinfunction "D13/SCK_16") (pintype "bidirectional"))
      (node (ref "U1") (pin "13") (pinfunction "CLK_13") (pintype "input"))
      (node (ref "U2") (pin "13") (pinfunction "CLK_13") (pintype "input"))
    )
    (net (code "35") (name "/SPI_SS_7SEG") (class "Default")
      (node (ref "MD1") (pin "13") (pinfunction "D10_13") (pintype "bidirectional"))
      (node (ref "U1") (pin "12") (pinfunction "~{CS}_12") (pintype "input"))
    )
    (net (code "36") (name "/SPI_SS_LEDS") (class "Default")
      (node (ref "MD1") (pin "12") (pinfunction "D9_12") (pintype "bidirectional"))
      (node (ref "U2") (pin "12") (pinfunction "~{CS}_12") (pintype "input"))
    )
    (net (code "37") (name "GND") (class "Default")
      (node (ref "C1") (pin "1") (pinfunction "1_1") (pintype "passive"))
      (node (ref "C2") (pin "1") (pinfunction "1_1") (pintype "passive"))
      (node (ref "C3") (pin "1") (pinfunction "1_1") (pintype "passive"))
      (node (ref "C4") (pin "1") (pinfunction "1_1") (pintype "passive"))
      (node (ref "MD1") (pin "29") (pinfunction "GND_29") (pintype "power_in"))
      (node (ref "MD1") (pin "4") (pinfunction "GND_4") (pintype "power_in"))
      (node (ref "P3") (pin "3") (pinfunction "3_3") (pintype "passive"))
      (node (ref "R2") (pin "1") (pinfunction "1_1") (pintype "passive"))
      (node (ref "R3") (pin "1") (pinfunction "1_1") (pintype "passive"))
      (node (ref "R4") (pin "1") (pinfunction "1_1") (pintype "passive"))
      (node (ref "U1") (pin "4") (pinfunction "GND_4") (pintype "power_in"))
      (node (ref "U1") (pin "9") (pinfunction "GND_9") (pintype "power_in"))
      (node (ref "U2") (pin "4") (pinfunction "GND_4") (pintype "power_in"))
      (node (ref "U2") (pin "9") (pinfunction "GND_9") (pintype "power_in"))
    )
    (net (code "38") (name "Net-(MD1-D2)") (class "Default")
      (node (ref "MD1") (pin "5") (pinfunction "D2_5") (pintype "bidirectional"))
      (node (ref "R2") (pin "2") (pinfunction "2_2") (pintype "passive"))
      (node (ref "SW3") (pin "1") (pinfunction "1_1") (pintype "passive"))
    )
    (net (code "39") (name "Net-(MD1-D3)") (class "Default")
      (node (ref "MD1") (pin "6") (pinfunction "D3_6") (pintype "bidirectional"))
      (node (ref "R3") (pin "2") (pinfunction "2_2") (pintype "passive"))
      (node (ref "SW2") (pin "1") (pinfunction "1_1") (pintype "passive"))
    )
    (net (code "40") (name "Net-(MD1-D4)") (class "Default")
      (node (ref "MD1") (pin "7") (pinfunction "D4_7") (pintype "bidirectional"))
      (node (ref "R4") (pin "2") (pinfunction "2_2") (pintype "passive"))
      (node (ref "SW1") (pin "1") (pinfunction "1_1") (pintype "passive"))
    )
    (net (code "41") (name "Net-(U1-ISET)") (class "Default")
      (node (ref "R1") (pin "1") (pinfunction "1_1") (pintype "passive"))
      (node (ref "U1") (pin "18") (pinfunction "ISET_18") (pintype "passive"))
    )
    (net (code "42") (name "Net-(U2-ISET)") (class "Default")
      (node (ref "R5") (pin "1") (pinfunction "1_1") (pintype "passive"))
      (node (ref "U2") (pin "18") (pinfunction "ISET_18") (pintype "passive"))
    )
    (net (code "43") (name "VCC") (class "Default")
      (node (ref "C1") (pin "2") (pinfunction "2_2") (pintype "passive"))
      (node (ref "C2") (pin "2") (pinfunction "2_2") (pintype "passive"))
      (node (ref "C3") (pin "2") (pinfunction "2_2") (pintype "passive"))
      (node (ref "C4") (pin "2") (pinfunction "2_2") (pintype "passive"))
      (node (ref "MD1") (pin "27") (pinfunction "+5V_27") (pintype "power_in"))
      (node (ref "P3") (pin "1") (pinfunction "1_1") (pintype "passive"))
      (node (ref "R1") (pin "2") (pinfunction "2_2") (pintype "passive"))
      (node (ref "R5") (pin "2") (pinfunction "2_2") (pintype "passive"))
      (node (ref "SW1") (pin "2") (pinfunction "2_2") (pintype "passive"))
      (node (ref "SW2") (pin "2") (pinfunction "2_2") (pintype "passive"))
      (node (ref "SW3") (pin "2") (pinfunction "2_2") (pintype "passive"))
      (node (ref "U1") (pin "19") (pinfunction "V+_19") (pintype "power_in"))
      (node (ref "U2") (pin "19") (pinfunction "V+_19") (pintype "power_in"))
    )
    (net (code "44") (name "unconnected-(MD1-+3V3-Pad17)") (class "Default")
      (node (ref "MD1") (pin "17") (pinfunction "+3V3_17") (pintype "power_in+no_connect"))
    )
    (net (code "45") (name "unconnected-(MD1-A0-Pad19)") (class "Default")
      (node (ref "MD1") (pin "19") (pinfunction "A0_19") (pintype "bidirectional+no_connect"))
    )
    (net (code "46") (name "unconnected-(MD1-A1-Pad20)") (class "Default")
      (node (ref "MD1") (pin "20") (pinfunction "A1_20") (pintype "bidirectional+no_connect"))
    )
    (net (code "47") (name "unconnected-(MD1-A2-Pad21)") (class "Default")
      (node (ref "MD1") (pin "21") (pinfunction "A2_21") (pintype "bidirectional+no_connect"))
    )
    (net (code "48") (name "unconnected-(MD1-A3-Pad22)") (class "Default")
      (node (ref "MD1") (pin "22") (pinfunction "A3_22") (pintype "bidirectional+no_connect"))
    )
    (net (code "49") (name "unconnected-(MD1-A6-Pad25)") (class "Default")
      (node (ref "MD1") (pin "25") (pinfunction "A6_25") (pintype "bidirectional+no_connect"))
    )
    (net (code "50") (name "unconnected-(MD1-A7-Pad26)") (class "Default")
      (node (ref "MD1") (pin "26") (pinfunction "A7_26") (pintype "bidirectional+no_connect"))
    )
    (net (code "51") (name "unconnected-(MD1-AREF-Pad18)") (class "Default")
      (node (ref "MD1") (pin "18") (pinfunction "AREF_18") (pintype "passive+no_connect"))
    )
    (net (code "52") (name "unconnected-(MD1-D0{slash}RX-Pad2)") (class "Default")
      (node (ref "MD1") (pin "2") (pinfunction "D0/RX_2") (pintype "bidirectional+no_connect"))
    )
    (net (code "53") (name "unconnected-(MD1-D1{slash}TX-Pad1)") (class "Default")
      (node (ref "MD1") (pin "1") (pinfunction "D1/TX_1") (pintype "bidirectional+no_connect"))
    )
    (net (code "54") (name "unconnected-(MD1-D6-Pad9)") (class "Default")
      (node (ref "MD1") (pin "9") (pinfunction "D6_9") (pintype "bidirectional+no_connect"))
    )
    (net (code "55") (name "unconnected-(MD1-D7-Pad10)") (class "Default")
      (node (ref "MD1") (pin "10") (pinfunction "D7_10") (pintype "bidirectional+no_connect"))
    )
    (net (code "56") (name "unconnected-(MD1-D8-Pad11)") (class "Default")
      (node (ref "MD1") (pin "11") (pinfunction "D8_11") (pintype "bidirectional+no_connect"))
    )
    (net (code "57") (name "unconnected-(MD1-VIN-Pad30)") (class "Default")
      (node (ref "MD1") (pin "30") (pinfunction "VIN_30") (pintype "power_in+no_connect"))
    )
    (net (code "58") (name "unconnected-(MD1-~{RESET}-Pad3)") (class "Default")
      (node (ref "MD1") (pin "3") (pinfunction "~{RESET}_3") (pintype "input+no_connect"))
    )
    (net (code "59") (name "unconnected-(MD1-~{RESET}-Pad28)") (class "Default")
      (node (ref "MD1") (pin "28") (pinfunction "~{RESET}_28") (pintype "input+no_connect"))
    )
    (net (code "60") (name "unconnected-(P3-Pad2)") (class "Default")
      (node (ref "P3") (pin "2") (pinfunction "2_2") (pintype "passive+no_connect"))
    )
    (net (code "61") (name "unconnected-(U1-DIG_4-Pad3)") (class "Default")
      (node (ref "U1") (pin "3") (pinfunction "DIG_4_3") (pintype "passive"))
    )
    (net (code "62") (name "unconnected-(U1-DIG_5-Pad10)") (class "Default")
      (node (ref "U1") (pin "10") (pinfunction "DIG_5_10") (pintype "passive"))
    )
    (net (code "63") (name "unconnected-(U1-DIG_6-Pad5)") (class "Default")
      (node (ref "U1") (pin "5") (pinfunction "DIG_6_5") (pintype "passive"))
    )
    (net (code "64") (name "unconnected-(U1-DIG_7-Pad8)") (class "Default")
      (node (ref "U1") (pin "8") (pinfunction "DIG_7_8") (pintype "passive"))
    )
  )
)
